# skylift-02_logo.net
KiCad netlist of a schematic drawn in EAGLE
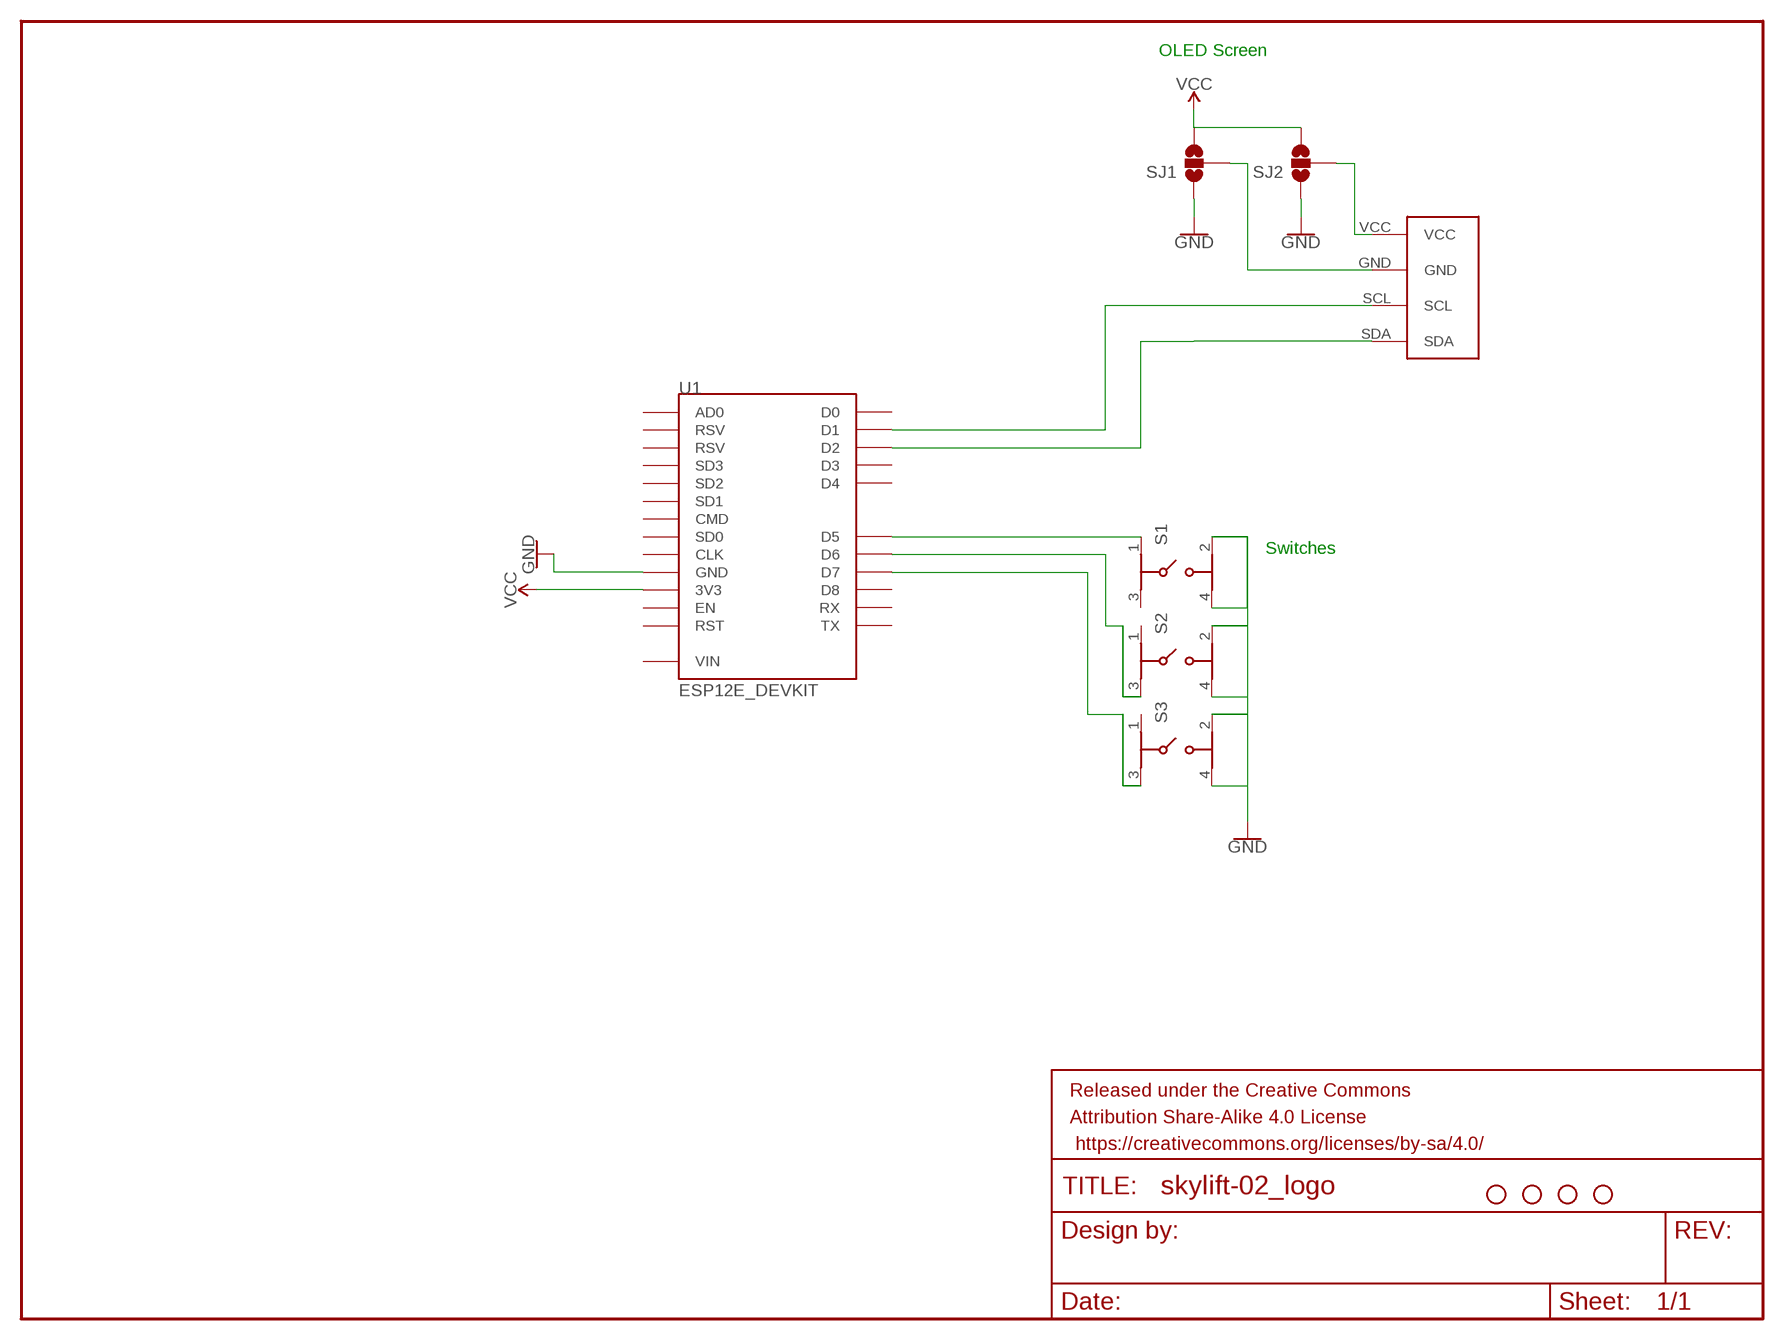
[diagram p0: schematic, sheet 1]

(export (version "E")
  (design (tool "Eeschema 10.0.6"))
  (components
    (comp (ref "FRAME1")
      (value "FRAME-LETTERNO_PACKAGE")
      (footprint "eagle-import:DUMMY")
      (fields (field (name "DESIGNER") "Nobody"))
      (libsource (lib "eagle-import") (part "FRAME-LETTERNO_PACKAGE"))
    )
    (comp (ref "H1")
      (value "STAND-OFFTIGHT")
      (footprint "eagle-import:STAND-OFF-TIGHT")
      (libsource (lib "eagle-import") (part "STAND-OFFTIGHT"))
    )
    (comp (ref "H2")
      (value "STAND-OFFTIGHT")
      (footprint "eagle-import:STAND-OFF-TIGHT")
      (libsource (lib "eagle-import") (part "STAND-OFFTIGHT"))
    )
    (comp (ref "H3")
      (value "STAND-OFFTIGHT")
      (footprint "eagle-import:STAND-OFF-TIGHT")
      (libsource (lib "eagle-import") (part "STAND-OFFTIGHT"))
    )
    (comp (ref "H4")
      (value "STAND-OFFTIGHT")
      (footprint "eagle-import:STAND-OFF-TIGHT")
      (libsource (lib "eagle-import") (part "STAND-OFFTIGHT"))
    )
    (comp (ref "S1")
      (value "436333045822")
      (footprint "eagle-import:436333045822")
      (libsource (lib "eagle-import") (part "436333045822"))
    )
    (comp (ref "S2")
      (value "436333045822")
      (footprint "eagle-import:436333045822")
      (libsource (lib "eagle-import") (part "436333045822"))
    )
    (comp (ref "S3")
      (value "436333045822")
      (footprint "eagle-import:436333045822")
      (libsource (lib "eagle-import") (part "436333045822"))
    )
    (comp (ref "SJ1")
      (value "SOLDERJUMPER_2WAY-OLDT")
      (footprint "eagle-import:SJ_2")
      (libsource (lib "eagle-import") (part "SOLDERJUMPER_2WAY-OLDT"))
    )
    (comp (ref "SJ2")
      (value "SOLDERJUMPER_2WAY-OLDT")
      (footprint "eagle-import:SJ_2")
      (libsource (lib "eagle-import") (part "SOLDERJUMPER_2WAY-OLDT"))
    )
    (comp (ref "U1")
      (value "ESP12E_DEVKIT")
      (footprint "eagle-import:ESP12E_DEVKIT")
      (libsource (lib "eagle-import") (part "ESP12E_DEVKIT"))
    )
    (comp (ref "U2")
      (value "I2C_OLED")
      (footprint "eagle-import:I2C_OLED_PACKAGE")
      (libsource (lib "eagle-import") (part "I2C_OLED"))
    )
  )
  (nets
    (net (code "1") (name "/VIN") (class "Default")
      (node (ref "U1") (pin "VIN") (pinfunction "VIN_VIN") (pintype "power_in"))
    )
    (net (code "2") (name "GND") (class "Default")
      (node (ref "S1") (pin "2") (pinfunction "4_2") (pintype "passive"))
      (node (ref "S1") (pin "4") (pinfunction "2_4") (pintype "passive"))
      (node (ref "S2") (pin "2") (pinfunction "4_2") (pintype "passive"))
      (node (ref "S2") (pin "4") (pinfunction "2_4") (pintype "passive"))
      (node (ref "S3") (pin "2") (pinfunction "4_2") (pintype "passive"))
      (node (ref "S3") (pin "4") (pinfunction "2_4") (pintype "passive"))
      (node (ref "SJ1") (pin "1") (pinfunction "1_1") (pintype "passive"))
      (node (ref "SJ2") (pin "1") (pinfunction "1_1") (pintype "passive"))
      (node (ref "U1") (pin "GND@0") (pinfunction "GND_GND@0") (pintype "power_in"))
      (node (ref "U1") (pin "GND@1") (pinfunction "GND_GND@1") (pintype "power_in"))
      (node (ref "U1") (pin "GND@2") (pinfunction "GND_GND@2") (pintype "power_in"))
      (node (ref "U1") (pin "GND@3") (pinfunction "GND_GND@3") (pintype "power_in"))
    )
    (net (code "3") (name "Net-(S1-3)") (class "Default")
      (node (ref "S1") (pin "1") (pinfunction "3_1") (pintype "passive"))
      (node (ref "U1") (pin "D5") (pinfunction "D5_D5") (pintype "bidirectional"))
    )
    (net (code "4") (name "Net-(S2-1)") (class "Default")
      (node (ref "S2") (pin "3") (pinfunction "1_3") (pintype "passive"))
      (node (ref "U1") (pin "D6") (pinfunction "D6_D6") (pintype "bidirectional"))
    )
    (net (code "5") (name "Net-(S3-1)") (class "Default")
      (node (ref "S3") (pin "3") (pinfunction "1_3") (pintype "passive"))
      (node (ref "U1") (pin "D7") (pinfunction "D7_D7") (pintype "bidirectional"))
    )
    (net (code "6") (name "Net-(SJ1-Pad2)") (class "Default")
      (node (ref "SJ1") (pin "2") (pinfunction "2_2") (pintype "passive"))
      (node (ref "U2") (pin "GND") (pinfunction "GND_GND") (pintype "bidirectional"))
    )
    (net (code "7") (name "Net-(SJ2-Pad2)") (class "Default")
      (node (ref "SJ2") (pin "2") (pinfunction "2_2") (pintype "passive"))
      (node (ref "U2") (pin "VCC") (pinfunction "VCC_VCC") (pintype "bidirectional"))
    )
    (net (code "8") (name "Net-(U1-PadD1)") (class "Default")
      (node (ref "U1") (pin "D1") (pinfunction "D1_D1") (pintype "bidirectional"))
      (node (ref "U2") (pin "SCL") (pinfunction "SCL_SCL") (pintype "bidirectional"))
    )
    (net (code "9") (name "Net-(U1-PadD2)") (class "Default")
      (node (ref "U1") (pin "D2") (pinfunction "D2_D2") (pintype "bidirectional"))
      (node (ref "U2") (pin "SDA") (pinfunction "SDA_SDA") (pintype "bidirectional"))
    )
    (net (code "10") (name "VCC") (class "Default")
      (node (ref "SJ1") (pin "3") (pinfunction "3_3") (pintype "passive"))
      (node (ref "SJ2") (pin "3") (pinfunction "3_3") (pintype "passive"))
      (node (ref "U1") (pin "3V3@0") (pinfunction "3V3_3V3@0") (pintype "power_in"))
      (node (ref "U1") (pin "3V3@1") (pinfunction "3V3_3V3@1") (pintype "power_in"))
      (node (ref "U1") (pin "3V3@2") (pinfunction "3V3_3V3@2") (pintype "power_in"))
    )
    (net (code "11") (name "unconnected-(S1-1-Pad3)") (class "Default")
      (node (ref "S1") (pin "3") (pinfunction "1_3") (pintype "passive"))
    )
    (net (code "12") (name "unconnected-(S2-3-Pad1)") (class "Default")
      (node (ref "S2") (pin "1") (pinfunction "3_1") (pintype "passive"))
    )
    (net (code "13") (name "unconnected-(S3-3-Pad1)") (class "Default")
      (node (ref "S3") (pin "1") (pinfunction "3_1") (pintype "passive"))
    )
    (net (code "14") (name "unconnected-(U1-PadAD0)") (class "Default")
      (node (ref "U1") (pin "AD0") (pinfunction "AD0_AD0") (pintype "bidirectional"))
    )
    (net (code "15") (name "unconnected-(U1-PadCLK)") (class "Default")
      (node (ref "U1") (pin "CLK") (pinfunction "CLK_CLK") (pintype "bidirectional"))
    )
    (net (code "16") (name "unconnected-(U1-PadCMD)") (class "Default")
      (node (ref "U1") (pin "CMD") (pinfunction "CMD_CMD") (pintype "bidirectional"))
    )
    (net (code "17") (name "unconnected-(U1-PadD0)") (class "Default")
      (node (ref "U1") (pin "D0") (pinfunction "D0_D0") (pintype "bidirectional"))
    )
    (net (code "18") (name "unconnected-(U1-PadD3)") (class "Default")
      (node (ref "U1") (pin "D3") (pinfunction "D3_D3") (pintype "bidirectional"))
    )
    (net (code "19") (name "unconnected-(U1-PadD4)") (class "Default")
      (node (ref "U1") (pin "D4") (pinfunction "D4_D4") (pintype "bidirectional"))
    )
    (net (code "20") (name "unconnected-(U1-PadD8)") (class "Default")
      (node (ref "U1") (pin "D8") (pinfunction "D8_D8") (pintype "bidirectional"))
    )
    (net (code "21") (name "unconnected-(U1-PadEN)") (class "Default")
      (node (ref "U1") (pin "EN") (pinfunction "EN_EN") (pintype "bidirectional"))
    )
    (net (code "22") (name "unconnected-(U1-PadRST)") (class "Default")
      (node (ref "U1") (pin "RST") (pinfunction "RST_RST") (pintype "bidirectional"))
    )
    (net (code "23") (name "unconnected-(U1-PadRX)") (class "Default")
      (node (ref "U1") (pin "RX") (pinfunction "RX_RX") (pintype "bidirectional"))
    )
    (net (code "24") (name "unconnected-(U1-PadSD0)") (class "Default")
      (node (ref "U1") (pin "SD0") (pinfunction "SD0_SD0") (pintype "bidirectional"))
    )
    (net (code "25") (name "unconnected-(U1-PadSD1)") (class "Default")
      (node (ref "U1") (pin "SD1") (pinfunction "SD1_SD1") (pintype "bidirectional"))
    )
    (net (code "26") (name "unconnected-(U1-PadSD2)") (class "Default")
      (node (ref "U1") (pin "SD2") (pinfunction "SD2_SD2") (pintype "bidirectional"))
    )
    (net (code "27") (name "unconnected-(U1-PadSD3)") (class "Default")
      (node (ref "U1") (pin "SD3") (pinfunction "SD3_SD3") (pintype "bidirectional"))
    )
    (net (code "28") (name "unconnected-(U1-PadTX)") (class "Default")
      (node (ref "U1") (pin "TX") (pinfunction "TX_TX") (pintype "bidirectional"))
    )
    (net (code "29") (name "unconnected-(U1-RSV-PadRSV@0)") (class "Default")
      (node (ref "U1") (pin "RSV@0") (pinfunction "RSV_RSV@0") (pintype "bidirectional"))
    )
    (net (code "30") (name "unconnected-(U1-RSV-PadRSV@1)") (class "Default")
      (node (ref "U1") (pin "RSV@1") (pinfunction "RSV_RSV@1") (pintype "bidirectional"))
    )
  )
)
